# trim_switch.net
KiCad netlist of a schematic drawn in EAGLE
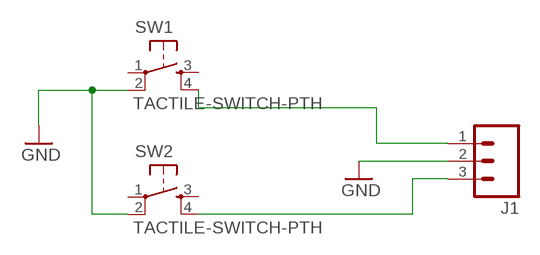
[diagram p0: schematic, sheet 1]

(export (version "E")
  (design (tool "Eeschema 10.0.6"))
  (components
    (comp (ref "J1")
      (value "M03PTH")
      (footprint "eagle-import:1X03")
      (libsource (lib "eagle-import") (part "M03PTH"))
    )
    (comp (ref "SW1")
      (value "TACTILE-SWITCH-PTH")
      (footprint "eagle-import:TAC-SWITCH-PTH")
      (libsource (lib "eagle-import") (part "TACTILE-SWITCH-PTH"))
    )
    (comp (ref "SW2")
      (value "TACTILE-SWITCH-PTH")
      (footprint "eagle-import:TAC-SWITCH-PTH")
      (libsource (lib "eagle-import") (part "TACTILE-SWITCH-PTH"))
    )
  )
  (nets
    (net (code "1") (name "GND") (class "Default")
      (node (ref "J1") (pin "2") (pinfunction "2_2") (pintype "passive"))
      (node (ref "SW1") (pin "2") (pinfunction "2_2") (pintype "passive"))
      (node (ref "SW2") (pin "2") (pinfunction "2_2") (pintype "passive"))
    )
    (net (code "2") (name "Net-(J1-Pad1)") (class "Default")
      (node (ref "J1") (pin "1") (pinfunction "1_1") (pintype "passive"))
      (node (ref "SW1") (pin "4") (pinfunction "4_4") (pintype "passive"))
    )
    (net (code "3") (name "Net-(J1-Pad3)") (class "Default")
      (node (ref "J1") (pin "3") (pinfunction "3_3") (pintype "passive"))
      (node (ref "SW2") (pin "4") (pinfunction "4_4") (pintype "passive"))
    )
    (net (code "4") (name "unconnected-(SW1-Pad1)") (class "Default")
      (node (ref "SW1") (pin "1") (pinfunction "1_1") (pintype "passive"))
    )
    (net (code "5") (name "unconnected-(SW1-Pad3)") (class "Default")
      (node (ref "SW1") (pin "3") (pinfunction "3_3") (pintype "passive"))
    )
    (net (code "6") (name "unconnected-(SW2-Pad1)") (class "Default")
      (node (ref "SW2") (pin "1") (pinfunction "1_1") (pintype "passive"))
    )
    (net (code "7") (name "unconnected-(SW2-Pad3)") (class "Default")
      (node (ref "SW2") (pin "3") (pinfunction "3_3") (pintype "passive"))
    )
  )
)
